# atx_psu_distributor_v2_0.net
KiCad netlist of a schematic drawn in EAGLE
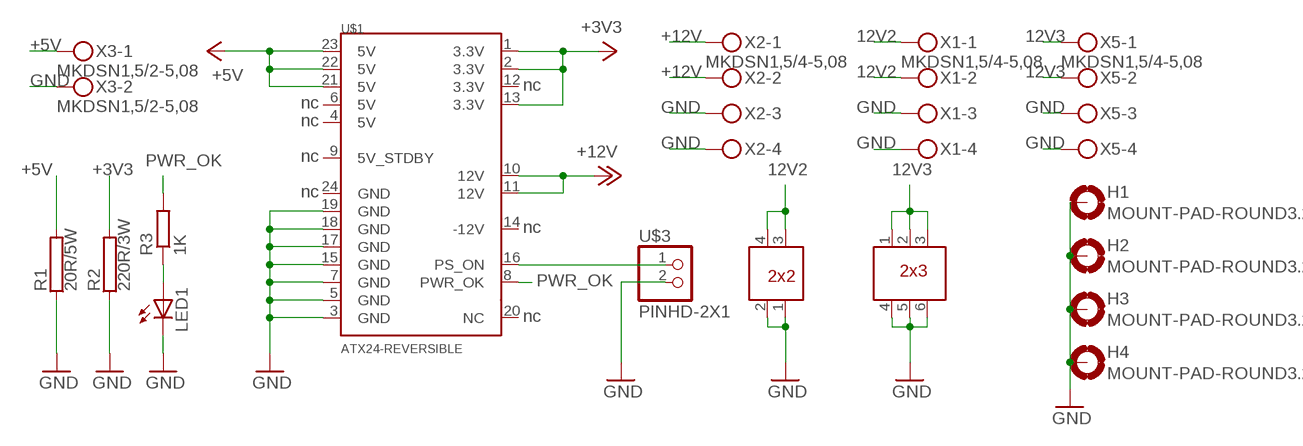
[diagram p0: schematic, sheet 1]

(export (version "E")
  (design (tool "Eeschema 10.0.6"))
  (components
    (comp (ref "H1")
      (value "MOUNT-PAD-ROUND3.2")
      (footprint "eagle-import:3,2-PAD")
      (libsource (lib "eagle-import") (part "MOUNT-PAD-ROUND3.2"))
    )
    (comp (ref "H2")
      (value "MOUNT-PAD-ROUND3.2")
      (footprint "eagle-import:3,2-PAD")
      (libsource (lib "eagle-import") (part "MOUNT-PAD-ROUND3.2"))
    )
    (comp (ref "H3")
      (value "MOUNT-PAD-ROUND3.2")
      (footprint "eagle-import:3,2-PAD")
      (libsource (lib "eagle-import") (part "MOUNT-PAD-ROUND3.2"))
    )
    (comp (ref "H4")
      (value "MOUNT-PAD-ROUND3.2")
      (footprint "eagle-import:3,2-PAD")
      (libsource (lib "eagle-import") (part "MOUNT-PAD-ROUND3.2"))
    )
    (comp (ref "LED1")
      (value "LED3MM")
      (footprint "eagle-import:LED3MM")
      (libsource (lib "eagle-import") (part "LED3MM"))
    )
    (comp (ref "R1")
      (value "20R/5W")
      (footprint "eagle-import:HPS923")
      (libsource (lib "eagle-import") (part "RHPS923"))
    )
    (comp (ref "R2")
      (value "220R/3W")
      (footprint "eagle-import:CA4050")
      (libsource (lib "eagle-import") (part "RCA4050"))
    )
    (comp (ref "R3")
      (value "1K")
      (footprint "eagle-import:0207_10")
      (libsource (lib "eagle-import") (part "R-EU_0207/10"))
    )
    (comp (ref "U$1")
      (value "ATX24-REVERSIBLE")
      (footprint "eagle-import:ATX24")
      (libsource (lib "eagle-import") (part "ATX24-REVERSIBLE"))
    )
    (comp (ref "U$2")
      (value "ATX2X2")
      (footprint "eagle-import:ATX2X2")
      (libsource (lib "eagle-import") (part "ATX2X2"))
    )
    (comp (ref "U$3")
      (value "PINHD-2X1")
      (footprint "eagle-import:PINHD-2X1")
      (libsource (lib "eagle-import") (part "PINHD-2X1"))
    )
    (comp (ref "U$4")
      (value "ATX2X3")
      (footprint "eagle-import:ATX2X3")
      (libsource (lib "eagle-import") (part "ATX2X3"))
    )
    (comp (ref "X1")
      (value "MKDSN1,5/4-5,08")
      (footprint "eagle-import:MKDSN1,5_4-5,08")
      (fields (field (name "MPN") "SMKDSN1,5/4-5,08"))
      (libsource (lib "eagle-import") (part "MKDSN1,5/4-5,08"))
    )
    (comp (ref "X2")
      (value "MKDSN1,5/4-5,08")
      (footprint "eagle-import:MKDSN1,5_4-5,08")
      (fields (field (name "MPN") "SMKDSN1,5/4-5,08"))
      (libsource (lib "eagle-import") (part "MKDSN1,5/4-5,08"))
    )
    (comp (ref "X3")
      (value "MKDSN1,5/2-5,08")
      (footprint "eagle-import:MKDSN1,5_2-5,08")
      (fields (field (name "MPN") "MKDSN 1,5/2-5.08"))
      (libsource (lib "eagle-import") (part "MKDSN1,5/2-5,08"))
    )
    (comp (ref "X5")
      (value "MKDSN1,5/4-5,08")
      (footprint "eagle-import:MKDSN1,5_4-5,08")
      (fields (field (name "MPN") "SMKDSN1,5/4-5,08"))
      (libsource (lib "eagle-import") (part "MKDSN1,5/4-5,08"))
    )
  )
  (nets
    (net (code "1") (name "+3V3") (class "Default")
      (node (ref "R2") (pin "2") (pinfunction "2_2") (pintype "passive"))
      (node (ref "U$1") (pin "1") (pinfunction "3.3V_1") (pintype "bidirectional"))
      (node (ref "U$1") (pin "13") (pinfunction "3.3V_13") (pintype "bidirectional"))
      (node (ref "U$1") (pin "2") (pinfunction "3.3V_2") (pintype "bidirectional"))
    )
    (net (code "2") (name "+5V") (class "Default")
      (node (ref "R1") (pin "2") (pinfunction "2_2") (pintype "passive"))
      (node (ref "U$1") (pin "21") (pinfunction "5V_21") (pintype "bidirectional"))
      (node (ref "U$1") (pin "22") (pinfunction "5V_22") (pintype "bidirectional"))
      (node (ref "U$1") (pin "23") (pinfunction "5V_23") (pintype "bidirectional"))
      (node (ref "X3") (pin "1") (pinfunction "KL_1") (pintype "passive"))
    )
    (net (code "3") (name "+12V") (class "Default")
      (node (ref "U$1") (pin "10") (pinfunction "12V_10") (pintype "bidirectional"))
      (node (ref "U$1") (pin "11") (pinfunction "12V_11") (pintype "bidirectional"))
      (node (ref "X2") (pin "1") (pinfunction "KL_1") (pintype "passive"))
      (node (ref "X2") (pin "2") (pinfunction "KL_2") (pintype "passive"))
    )
    (net (code "4") (name "/12V2") (class "Default")
      (node (ref "U$2") (pin "3") (pinfunction "P$3_3") (pintype "bidirectional"))
      (node (ref "U$2") (pin "4") (pinfunction "P$4_4") (pintype "bidirectional"))
      (node (ref "X1") (pin "1") (pinfunction "KL_1") (pintype "passive"))
      (node (ref "X1") (pin "2") (pinfunction "KL_2") (pintype "passive"))
    )
    (net (code "5") (name "/12V3") (class "Default")
      (node (ref "U$4") (pin "1") (pinfunction "P$1_1") (pintype "bidirectional"))
      (node (ref "U$4") (pin "2") (pinfunction "P$2_2") (pintype "bidirectional"))
      (node (ref "U$4") (pin "3") (pinfunction "P$3_3") (pintype "bidirectional"))
      (node (ref "X5") (pin "1") (pinfunction "KL_1") (pintype "passive"))
      (node (ref "X5") (pin "2") (pinfunction "KL_2") (pintype "passive"))
    )
    (net (code "6") (name "/PWR_OK") (class "Default")
      (node (ref "R3") (pin "2") (pinfunction "2_2") (pintype "passive"))
      (node (ref "U$1") (pin "8") (pinfunction "PWR_OK_8") (pintype "bidirectional"))
    )
    (net (code "7") (name "GND") (class "Default")
      (node (ref "H1") (pin "B3,2") (pinfunction "MOUNT_B3,2") (pintype "passive"))
      (node (ref "H2") (pin "B3,2") (pinfunction "MOUNT_B3,2") (pintype "passive"))
      (node (ref "H3") (pin "B3,2") (pinfunction "MOUNT_B3,2") (pintype "passive"))
      (node (ref "H4") (pin "B3,2") (pinfunction "MOUNT_B3,2") (pintype "passive"))
      (node (ref "LED1") (pin "K") (pinfunction "C_K") (pintype "passive"))
      (node (ref "R1") (pin "1") (pinfunction "1_1") (pintype "passive"))
      (node (ref "R2") (pin "1") (pinfunction "1_1") (pintype "passive"))
      (node (ref "U$1") (pin "15") (pinfunction "GND_15") (pintype "bidirectional"))
      (node (ref "U$1") (pin "17") (pinfunction "GND_17") (pintype "bidirectional"))
      (node (ref "U$1") (pin "18") (pinfunction "GND_18") (pintype "bidirectional"))
      (node (ref "U$1") (pin "19") (pinfunction "GND_19") (pintype "bidirectional"))
      (node (ref "U$1") (pin "3") (pinfunction "GND_3") (pintype "bidirectional"))
      (node (ref "U$1") (pin "5") (pinfunction "GND_5") (pintype "bidirectional"))
      (node (ref "U$1") (pin "7") (pinfunction "GND_7") (pintype "bidirectional"))
      (node (ref "U$2") (pin "1") (pinfunction "P$1_1") (pintype "bidirectional"))
      (node (ref "U$2") (pin "2") (pinfunction "P$2_2") (pintype "bidirectional"))
      (node (ref "U$3") (pin "2") (pinfunction "2_2") (pintype "passive"))
      (node (ref "U$4") (pin "4") (pinfunction "P$4_4") (pintype "bidirectional"))
      (node (ref "U$4") (pin "5") (pinfunction "P$5_5") (pintype "bidirectional"))
      (node (ref "U$4") (pin "6") (pinfunction "P$6_6") (pintype "bidirectional"))
      (node (ref "X1") (pin "3") (pinfunction "KL_3") (pintype "passive"))
      (node (ref "X1") (pin "4") (pinfunction "KL_4") (pintype "passive"))
      (node (ref "X2") (pin "3") (pinfunction "KL_3") (pintype "passive"))
      (node (ref "X2") (pin "4") (pinfunction "KL_4") (pintype "passive"))
      (node (ref "X3") (pin "2") (pinfunction "KL_2") (pintype "passive"))
      (node (ref "X5") (pin "3") (pinfunction "KL_3") (pintype "passive"))
      (node (ref "X5") (pin "4") (pinfunction "KL_4") (pintype "passive"))
    )
    (net (code "8") (name "Net-(LED1-PadA)") (class "Default")
      (node (ref "LED1") (pin "A") (pinfunction "A_A") (pintype "passive"))
      (node (ref "R3") (pin "1") (pinfunction "1_1") (pintype "passive"))
    )
    (net (code "9") (name "Net-(U$1-PS_ON)") (class "Default")
      (node (ref "U$1") (pin "16") (pinfunction "PS_ON_16") (pintype "bidirectional"))
      (node (ref "U$3") (pin "1") (pinfunction "1_1") (pintype "passive"))
    )
    (net (code "10") (name "unconnected-(U$1--12V-Pad14)") (class "Default")
      (node (ref "U$1") (pin "14") (pinfunction "-12V_14") (pintype "bidirectional"))
    )
    (net (code "11") (name "unconnected-(U$1-3.3V-Pad12)") (class "Default")
      (node (ref "U$1") (pin "12") (pinfunction "3.3V_12") (pintype "bidirectional"))
    )
    (net (code "12") (name "unconnected-(U$1-5V-Pad4)") (class "Default")
      (node (ref "U$1") (pin "4") (pinfunction "5V_4") (pintype "bidirectional"))
    )
    (net (code "13") (name "unconnected-(U$1-5V-Pad6)") (class "Default")
      (node (ref "U$1") (pin "6") (pinfunction "5V_6") (pintype "bidirectional"))
    )
    (net (code "14") (name "unconnected-(U$1-5V_STDBY-Pad9)") (class "Default")
      (node (ref "U$1") (pin "9") (pinfunction "5V_STDBY_9") (pintype "bidirectional"))
    )
    (net (code "15") (name "unconnected-(U$1-GND-Pad24)") (class "Default")
      (node (ref "U$1") (pin "24") (pinfunction "GND_24") (pintype "bidirectional"))
    )
    (net (code "16") (name "unconnected-(U$1-NC-Pad20)") (class "Default")
      (node (ref "U$1") (pin "20") (pinfunction "NC_20") (pintype "bidirectional"))
    )
  )
)
